# Gas.net
KiCad netlist of a schematic drawn in EAGLE
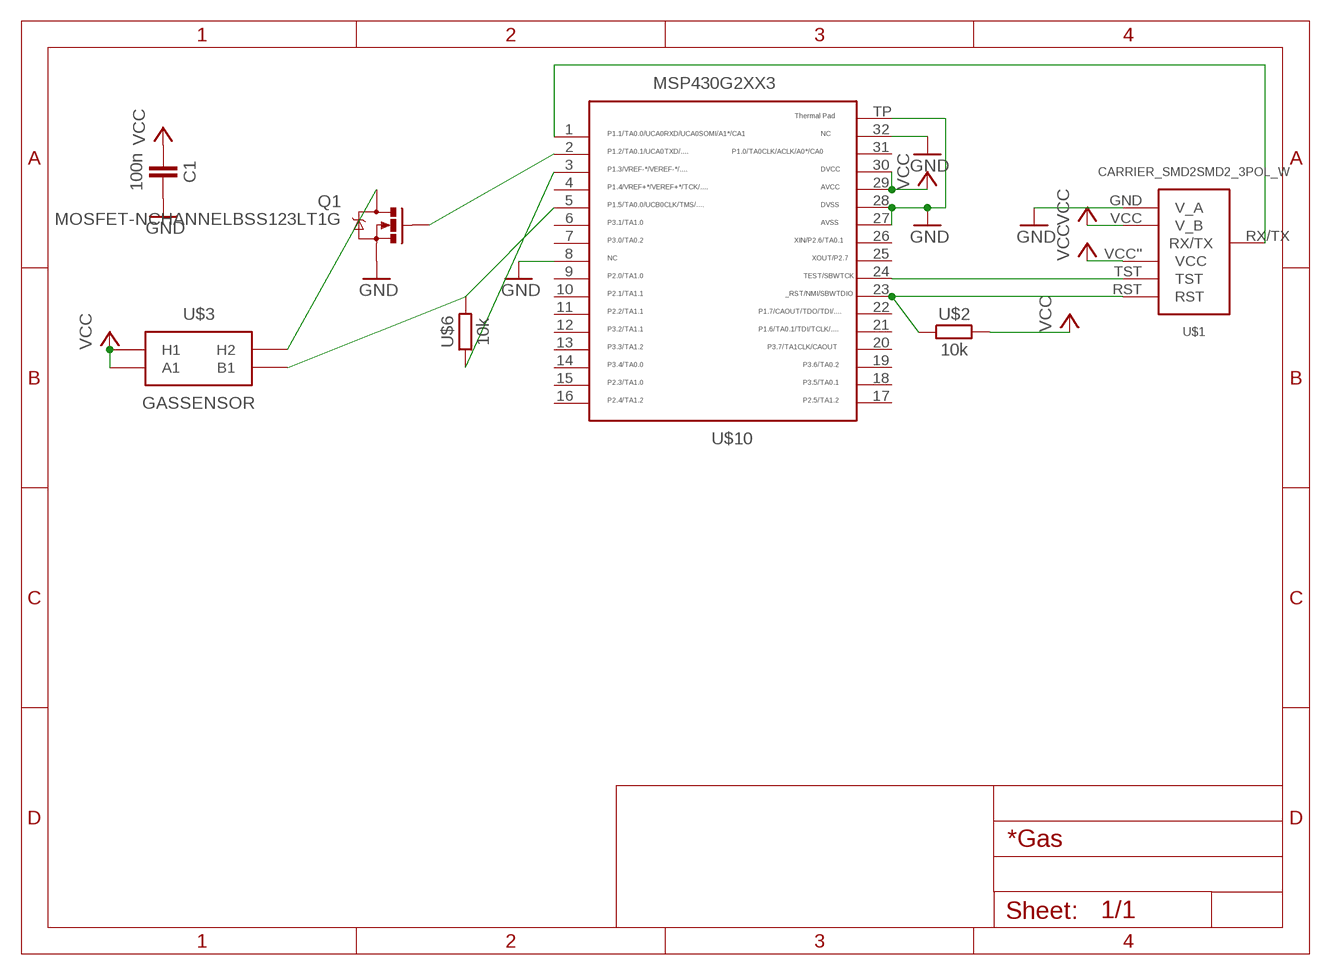
[diagram p0: schematic, sheet 1]

(export (version "E")
  (design (tool "Eeschema 10.0.6"))
  (components
    (comp (ref "C1")
      (value "100n")
      (footprint "eagle-import:603")
      (libsource (lib "eagle-import") (part "CAPACITOR"))
    )
    (comp (ref "Q1")
      (value "MOSFET-NCHANNELBSS123LT1G")
      (footprint "eagle-import:SOT23-3")
      (libsource (lib "eagle-import") (part "MOSFET-NCHANNELBSS123LT1G"))
    )
    (comp (ref "U$1")
      (value "CARRIER_SMD2SMD2_3POL_W")
      (footprint "eagle-import:CARRIER_SMD2_WIDE_3POL")
      (libsource (lib "eagle-import") (part "CARRIER_SMD2SMD2_3POL_W"))
    )
    (comp (ref "U$2")
      (value "10k")
      (footprint "eagle-import:603")
      (libsource (lib "eagle-import") (part "RESISTOR0603"))
    )
    (comp (ref "U$3")
      (value "GASSENSOR")
      (footprint "eagle-import:GASSENSOR")
      (libsource (lib "eagle-import") (part "GASSENSOR"))
    )
    (comp (ref "U$6")
      (value "10k")
      (footprint "eagle-import:603")
      (libsource (lib "eagle-import") (part "RESISTOR0603"))
    )
    (comp (ref "U$10")
      (value "MSP430G2553")
      (footprint "eagle-import:QFN32")
      (libsource (lib "eagle-import") (part "MSP430G2553"))
    )
  )
  (nets
    (net (code "1") (name "GND") (class "Default")
      (node (ref "C1") (pin "2") (pinfunction "2_2") (pintype "passive"))
      (node (ref "Q1") (pin "2") (pinfunction "S_2") (pintype "passive"))
      (node (ref "U$1") (pin "GND") (pinfunction "V_A_GND") (pintype "bidirectional"))
      (node (ref "U$10") (pin "27") (pinfunction "27_27") (pintype "bidirectional"))
      (node (ref "U$10") (pin "28") (pinfunction "28_28") (pintype "bidirectional"))
      (node (ref "U$10") (pin "32") (pinfunction "32_32") (pintype "bidirectional"))
      (node (ref "U$10") (pin "8") (pinfunction "8_8") (pintype "bidirectional"))
      (node (ref "U$10") (pin "TP") (pinfunction "TP_TP") (pintype "bidirectional"))
    )
    (net (code "2") (name "Net-(Q1-D)") (class "Default")
      (node (ref "Q1") (pin "3") (pinfunction "D_3") (pintype "passive"))
      (node (ref "U$3") (pin "PHB") (pinfunction "H2_PHB") (pintype "bidirectional"))
    )
    (net (code "3") (name "Net-(Q1-G)") (class "Default")
      (node (ref "Q1") (pin "1") (pinfunction "G_1") (pintype "passive"))
      (node (ref "U$10") (pin "2") (pinfunction "2_2") (pintype "bidirectional"))
    )
    (net (code "4") (name "Net-(U$1-PadRST)") (class "Default")
      (node (ref "U$1") (pin "RST") (pinfunction "RST_RST") (pintype "bidirectional"))
      (node (ref "U$10") (pin "23") (pinfunction "23_23") (pintype "bidirectional"))
      (node (ref "U$2") (pin "1") (pinfunction "1_1") (pintype "passive"))
    )
    (net (code "5") (name "Net-(U$1-PadRX{slash}TX)") (class "Default")
      (node (ref "U$1") (pin "RX/TX") (pinfunction "RX/TX_RX/TX") (pintype "bidirectional"))
      (node (ref "U$10") (pin "1") (pinfunction "1_1") (pintype "bidirectional"))
    )
    (net (code "6") (name "Net-(U$1-PadTST)") (class "Default")
      (node (ref "U$1") (pin "TST") (pinfunction "TST_TST") (pintype "bidirectional"))
      (node (ref "U$10") (pin "24") (pinfunction "24_24") (pintype "bidirectional"))
    )
    (net (code "7") (name "Net-(U$3-B1)") (class "Default")
      (node (ref "U$10") (pin "5") (pinfunction "5_5") (pintype "bidirectional"))
      (node (ref "U$3") (pin "PB1") (pinfunction "B1_PB1") (pintype "bidirectional"))
      (node (ref "U$6") (pin "2") (pinfunction "2_2") (pintype "passive"))
    )
    (net (code "8") (name "Net-(U$10-Pad3)") (class "Default")
      (node (ref "U$10") (pin "3") (pinfunction "3_3") (pintype "bidirectional"))
      (node (ref "U$6") (pin "1") (pinfunction "1_1") (pintype "passive"))
    )
    (net (code "9") (name "VCC") (class "Default")
      (node (ref "C1") (pin "1") (pinfunction "1_1") (pintype "passive"))
      (node (ref "U$1") (pin "VCC") (pinfunction "V_B_VCC") (pintype "bidirectional"))
      (node (ref "U$1") (pin "VCC''") (pinfunction "VCC_VCC''") (pintype "bidirectional"))
      (node (ref "U$10") (pin "29") (pinfunction "29_29") (pintype "bidirectional"))
      (node (ref "U$10") (pin "30") (pinfunction "30_30") (pintype "bidirectional"))
      (node (ref "U$2") (pin "2") (pinfunction "2_2") (pintype "passive"))
      (node (ref "U$3") (pin "PA1") (pinfunction "A1_PA1") (pintype "bidirectional"))
      (node (ref "U$3") (pin "PHA") (pinfunction "H1_PHA") (pintype "bidirectional"))
    )
    (net (code "10") (name "unconnected-(U$10-Pad4)") (class "Default")
      (node (ref "U$10") (pin "4") (pinfunction "4_4") (pintype "bidirectional"))
    )
    (net (code "11") (name "unconnected-(U$10-Pad6)") (class "Default")
      (node (ref "U$10") (pin "6") (pinfunction "6_6") (pintype "bidirectional"))
    )
    (net (code "12") (name "unconnected-(U$10-Pad7)") (class "Default")
      (node (ref "U$10") (pin "7") (pinfunction "7_7") (pintype "bidirectional"))
    )
    (net (code "13") (name "unconnected-(U$10-Pad9)") (class "Default")
      (node (ref "U$10") (pin "9") (pinfunction "9_9") (pintype "bidirectional"))
    )
    (net (code "14") (name "unconnected-(U$10-Pad10)") (class "Default")
      (node (ref "U$10") (pin "10") (pinfunction "10_10") (pintype "bidirectional"))
    )
    (net (code "15") (name "unconnected-(U$10-Pad11)") (class "Default")
      (node (ref "U$10") (pin "11") (pinfunction "11_11") (pintype "bidirectional"))
    )
    (net (code "16") (name "unconnected-(U$10-Pad12)") (class "Default")
      (node (ref "U$10") (pin "12") (pinfunction "12_12") (pintype "bidirectional"))
    )
    (net (code "17") (name "unconnected-(U$10-Pad13)") (class "Default")
      (node (ref "U$10") (pin "13") (pinfunction "13_13") (pintype "bidirectional"))
    )
    (net (code "18") (name "unconnected-(U$10-Pad14)") (class "Default")
      (node (ref "U$10") (pin "14") (pinfunction "14_14") (pintype "bidirectional"))
    )
    (net (code "19") (name "unconnected-(U$10-Pad15)") (class "Default")
      (node (ref "U$10") (pin "15") (pinfunction "15_15") (pintype "bidirectional"))
    )
    (net (code "20") (name "unconnected-(U$10-Pad16)") (class "Default")
      (node (ref "U$10") (pin "16") (pinfunction "16_16") (pintype "bidirectional"))
    )
    (net (code "21") (name "unconnected-(U$10-Pad17)") (class "Default")
      (node (ref "U$10") (pin "17") (pinfunction "17_17") (pintype "bidirectional"))
    )
    (net (code "22") (name "unconnected-(U$10-Pad18)") (class "Default")
      (node (ref "U$10") (pin "18") (pinfunction "18_18") (pintype "bidirectional"))
    )
    (net (code "23") (name "unconnected-(U$10-Pad19)") (class "Default")
      (node (ref "U$10") (pin "19") (pinfunction "19_19") (pintype "bidirectional"))
    )
    (net (code "24") (name "unconnected-(U$10-Pad20)") (class "Default")
      (node (ref "U$10") (pin "20") (pinfunction "20_20") (pintype "bidirectional"))
    )
    (net (code "25") (name "unconnected-(U$10-Pad21)") (class "Default")
      (node (ref "U$10") (pin "21") (pinfunction "21_21") (pintype "bidirectional"))
    )
    (net (code "26") (name "unconnected-(U$10-Pad22)") (class "Default")
      (node (ref "U$10") (pin "22") (pinfunction "22_22") (pintype "bidirectional"))
    )
    (net (code "27") (name "unconnected-(U$10-Pad25)") (class "Default")
      (node (ref "U$10") (pin "25") (pinfunction "25_25") (pintype "bidirectional"))
    )
    (net (code "28") (name "unconnected-(U$10-Pad26)") (class "Default")
      (node (ref "U$10") (pin "26") (pinfunction "26_26") (pintype "bidirectional"))
    )
    (net (code "29") (name "unconnected-(U$10-Pad31)") (class "Default")
      (node (ref "U$10") (pin "31") (pinfunction "31_31") (pintype "bidirectional"))
    )
  )
)
